# SensorModule.net
KiCad netlist of a schematic drawn in EAGLE
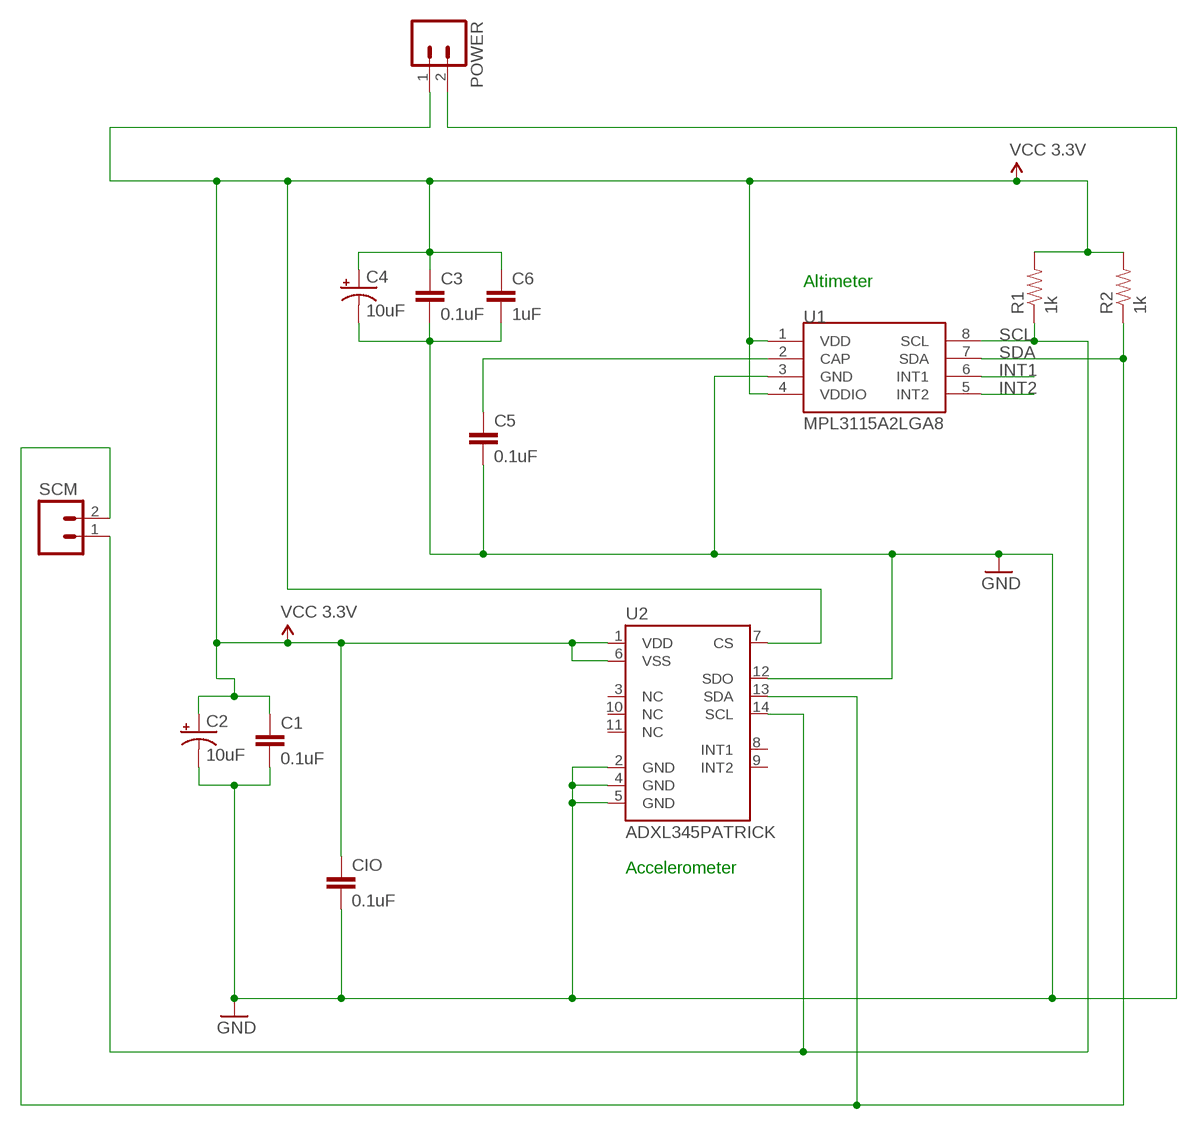
[diagram p0: schematic, sheet 1]

(export (version "E")
  (design (tool "Eeschema 10.0.6"))
  (components
    (comp (ref "C1")
      (value "0.1uF")
      (footprint "eagle-import:CAP-PTH-SMALL")
      (libsource (lib "eagle-import") (part "CAPPTH"))
    )
    (comp (ref "C2")
      (value "10uF")
      (footprint "eagle-import:CPOL-RADIAL-10UF-25V")
      (libsource (lib "eagle-import") (part "CAP_POLPTH2"))
    )
    (comp (ref "C3")
      (value "0.1uF")
      (footprint "eagle-import:CAP-PTH-SMALL")
      (libsource (lib "eagle-import") (part "CAPPTH"))
    )
    (comp (ref "C4")
      (value "10uF")
      (footprint "eagle-import:CPOL-RADIAL-10UF-25V")
      (libsource (lib "eagle-import") (part "CAP_POLPTH2"))
    )
    (comp (ref "C5")
      (value "0.1uF")
      (footprint "eagle-import:CAP-PTH-SMALL")
      (libsource (lib "eagle-import") (part "CAPPTH"))
    )
    (comp (ref "C6")
      (value "1uF")
      (footprint "eagle-import:CAP-PTH-SMALL")
      (libsource (lib "eagle-import") (part "CAPPTH"))
    )
    (comp (ref "CIO")
      (value "0.1uF")
      (footprint "eagle-import:CAP-PTH-SMALL")
      (libsource (lib "eagle-import") (part "CAPPTH"))
    )
    (comp (ref "POWER")
      (value "M02PTH")
      (footprint "eagle-import:1X02")
      (libsource (lib "eagle-import") (part "M02PTH"))
    )
    (comp (ref "R1")
      (value "1k")
      (footprint "eagle-import:AXIAL-0.4")
      (libsource (lib "eagle-import") (part "RESISTORPTH-1/4W"))
    )
    (comp (ref "R2")
      (value "1k")
      (footprint "eagle-import:AXIAL-0.4")
      (libsource (lib "eagle-import") (part "RESISTORPTH-1/4W"))
    )
    (comp (ref "SCM")
      (value "M02PTH")
      (footprint "eagle-import:1X02")
      (libsource (lib "eagle-import") (part "M02PTH"))
    )
    (comp (ref "U1")
      (value "MPL3115A2LGA8")
      (footprint "eagle-import:LGA8")
      (libsource (lib "eagle-import") (part "MPL3115A2LGA8"))
    )
    (comp (ref "U2")
      (value "ADXL345PATRICK")
      (footprint "eagle-import:LGA14_1_1_PATRICK")
      (libsource (lib "eagle-import") (part "ADXL345PATRICK"))
    )
  )
  (nets
    (net (code "1") (name "/INT1") (class "Default")
      (node (ref "U1") (pin "6") (pinfunction "INT1_6") (pintype "bidirectional"))
    )
    (net (code "2") (name "/INT2") (class "Default")
      (node (ref "U1") (pin "5") (pinfunction "INT2_5") (pintype "bidirectional"))
    )
    (net (code "3") (name "/SCL") (class "Default")
      (node (ref "R1") (pin "P$1") (pinfunction "1_P$1") (pintype "passive"))
      (node (ref "SCM") (pin "1") (pinfunction "1_1") (pintype "passive"))
      (node (ref "U1") (pin "8") (pinfunction "SCL_8") (pintype "bidirectional"))
      (node (ref "U2") (pin "14") (pinfunction "SCL_14") (pintype "bidirectional"))
    )
    (net (code "4") (name "/SDA") (class "Default")
      (node (ref "R2") (pin "P$1") (pinfunction "1_P$1") (pintype "passive"))
      (node (ref "SCM") (pin "2") (pinfunction "2_2") (pintype "passive"))
      (node (ref "U1") (pin "7") (pinfunction "SDA_7") (pintype "bidirectional"))
      (node (ref "U2") (pin "13") (pinfunction "SDA_13") (pintype "bidirectional"))
    )
    (net (code "5") (name "GND") (class "Default")
      (node (ref "C1") (pin "2") (pinfunction "2_2") (pintype "passive"))
      (node (ref "C2") (pin "2") (pinfunction "-_2") (pintype "passive"))
      (node (ref "C3") (pin "2") (pinfunction "2_2") (pintype "passive"))
      (node (ref "C4") (pin "2") (pinfunction "-_2") (pintype "passive"))
      (node (ref "C5") (pin "2") (pinfunction "2_2") (pintype "passive"))
      (node (ref "C6") (pin "2") (pinfunction "2_2") (pintype "passive"))
      (node (ref "CIO") (pin "2") (pinfunction "2_2") (pintype "passive"))
      (node (ref "POWER") (pin "2") (pinfunction "2_2") (pintype "passive"))
      (node (ref "U1") (pin "3") (pinfunction "GND_3") (pintype "bidirectional"))
      (node (ref "U2") (pin "12") (pinfunction "SDO_12") (pintype "bidirectional"))
      (node (ref "U2") (pin "2") (pinfunction "GND_2") (pintype "bidirectional"))
      (node (ref "U2") (pin "4") (pinfunction "GND_4") (pintype "bidirectional"))
      (node (ref "U2") (pin "5") (pinfunction "GND_5") (pintype "bidirectional"))
    )
    (net (code "6") (name "Net-(U1-CAP)") (class "Default")
      (node (ref "C5") (pin "1") (pinfunction "1_1") (pintype "passive"))
      (node (ref "U1") (pin "2") (pinfunction "CAP_2") (pintype "bidirectional"))
    )
    (net (code "7") (name "VCC 3.3V") (class "Default")
      (node (ref "C1") (pin "1") (pinfunction "1_1") (pintype "passive"))
      (node (ref "C2") (pin "1") (pinfunction "+_1") (pintype "passive"))
      (node (ref "C3") (pin "1") (pinfunction "1_1") (pintype "passive"))
      (node (ref "C4") (pin "1") (pinfunction "+_1") (pintype "passive"))
      (node (ref "C6") (pin "1") (pinfunction "1_1") (pintype "passive"))
      (node (ref "CIO") (pin "1") (pinfunction "1_1") (pintype "passive"))
      (node (ref "POWER") (pin "1") (pinfunction "1_1") (pintype "passive"))
      (node (ref "R1") (pin "P$2") (pinfunction "2_P$2") (pintype "passive"))
      (node (ref "R2") (pin "P$2") (pinfunction "2_P$2") (pintype "passive"))
      (node (ref "U1") (pin "1") (pinfunction "VDD_1") (pintype "bidirectional"))
      (node (ref "U1") (pin "4") (pinfunction "VDDIO_4") (pintype "bidirectional"))
      (node (ref "U2") (pin "1") (pinfunction "VDD_1") (pintype "bidirectional"))
      (node (ref "U2") (pin "6") (pinfunction "VSS_6") (pintype "bidirectional"))
      (node (ref "U2") (pin "7") (pinfunction "CS_7") (pintype "bidirectional"))
    )
    (net (code "8") (name "unconnected-(U2-INT1-Pad8)") (class "Default")
      (node (ref "U2") (pin "8") (pinfunction "INT1_8") (pintype "bidirectional"))
    )
    (net (code "9") (name "unconnected-(U2-INT2-Pad9)") (class "Default")
      (node (ref "U2") (pin "9") (pinfunction "INT2_9") (pintype "bidirectional"))
    )
    (net (code "10") (name "unconnected-(U2-NC-Pad3)") (class "Default")
      (node (ref "U2") (pin "3") (pinfunction "NC_3") (pintype "bidirectional"))
    )
    (net (code "11") (name "unconnected-(U2-NC-Pad10)") (class "Default")
      (node (ref "U2") (pin "10") (pinfunction "NC_10") (pintype "bidirectional"))
    )
    (net (code "12") (name "unconnected-(U2-NC-Pad11)") (class "Default")
      (node (ref "U2") (pin "11") (pinfunction "NC_11") (pintype "bidirectional"))
    )
  )
)
